# HTtransitorio.net
KiCad netlist of a schematic drawn in Altium Designer
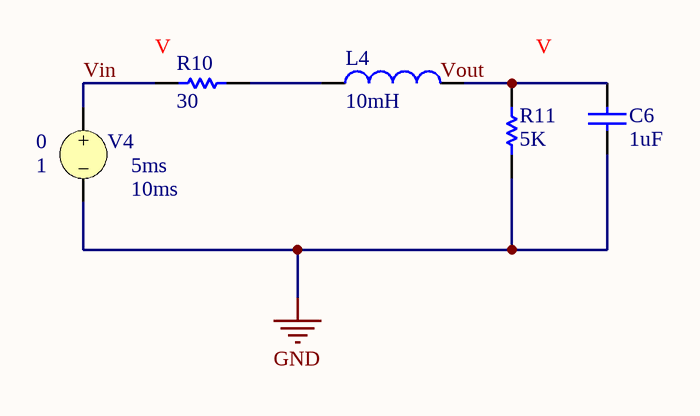
[diagram p0: HTtransitorio.SchDoc]

(export (version "E")
  (design (tool "Eeschema 10.0.6"))
  (components
    (comp (ref "C6")
      (value "1uF")
      (description "Capacitor")
      (libsource (lib "Simulation Generic Components") (part "Capacitor"))
    )
    (comp (ref "L4")
      (value "10mH")
      (description "Inductor")
      (libsource (lib "Simulation Generic Components") (part "Inductor"))
    )
    (comp (ref "R10")
      (value "30")
      (description "Resistor")
      (libsource (lib "Simulation Generic Components") (part "Resistor"))
    )
    (comp (ref "R11")
      (value "5K")
      (description "Resistor")
      (libsource (lib "Simulation Generic Components") (part "Resistor"))
    )
    (comp (ref "V4")
      (value "PULSE(0 1 100n 10n 10n 5ms 10ms 0)")
      (description "Voltage Source")
      (fields
        (field (name "INITIAL VALUE") "0")
        (field (name "PULSED VALUE") "1")
        (field (name "PULSE WIDTH") "5ms")
        (field (name "PERIOD") "10ms")
        (field (name "PUBLISHER") "Altium Limited")
      )
      (libsource (lib "Simulation Generic Components") (part "VSRC"))
    )
  )
  (nets
    (net (code "1") (name "/Vin") (class "Default")
      (node (ref "R10") (pin "2") (pinfunction "2_2") (pintype "passive"))
      (node (ref "V4") (pin "1") (pinfunction "1_1") (pintype "passive"))
    )
    (net (code "3") (name "GND") (class "Default")
      (node (ref "C6") (pin "1") (pinfunction "1_1") (pintype "passive"))
      (node (ref "R11") (pin "2") (pinfunction "2_2") (pintype "passive"))
      (node (ref "V4") (pin "2") (pinfunction "2_2") (pintype "passive"))
    )
    (net (code "4") (name "Net-(C6-Pad2)") (class "Default")
      (node (ref "C6") (pin "2") (pinfunction "2_2") (pintype "passive"))
      (node (ref "L4") (pin "2") (pinfunction "2_2") (pintype "passive"))
      (node (ref "R11") (pin "1") (pinfunction "1_1") (pintype "passive"))
    )
    (net (code "5") (name "Net-(L4-Pad1)") (class "Default")
      (node (ref "L4") (pin "1") (pinfunction "1_1") (pintype "passive"))
      (node (ref "R10") (pin "1") (pinfunction "1_1") (pintype "passive"))
    )
  )
)
